# power.net
KiCad netlist of a schematic drawn in Altium Designer
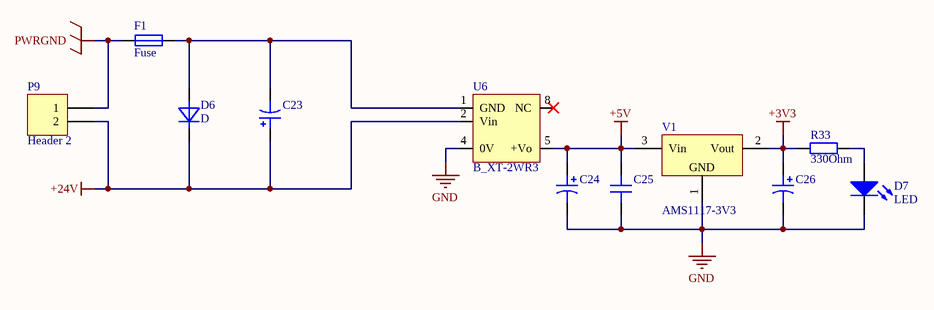
[diagram p0: power.SchDoc]

(export (version "E")
  (design (tool "Eeschema 10.0.6"))
  (components
    (comp (ref "C23")
      (value "1uF")
      (footprint "TC3528-1411")
      (description "Capacitor")
      (fields (field (name "PUBLISHER") "Altium Limited"))
      (libsource (lib "MiLib") (part "Cap Pol"))
    )
    (comp (ref "C24")
      (value "10uF")
      (footprint "TC3528-1411")
      (description "Capacitor")
      (fields (field (name "PUBLISHER") "Altium Limited"))
      (libsource (lib "MiLib") (part "Cap Pol"))
    )
    (comp (ref "C25")
      (value "100nF")
      (footprint "CAP 0805")
      (description "Non-polar capacitor")
      (fields (field (name "PUBLISHER") "Altium Limited"))
      (libsource (lib "MiLib") (part "Cap"))
    )
    (comp (ref "C26")
      (value "100uF")
      (footprint "TC7343-2917")
      (description "Capacitor")
      (fields (field (name "PUBLISHER") "Altium Limited"))
      (libsource (lib "MiLib") (part "Cap Pol"))
    )
    (comp (ref "D6") (value "D") (footprint "CD3216-1206") (libsource (lib "MiLib") (part "D")))
    (comp (ref "D7")
      (value "LED")
      (footprint "CD2012-0805")
      (fields (field (name "PUBLISHER") "Altium Limited"))
      (libsource (lib "MiLib") (part "LED"))
    )
    (comp (ref "F1")
      (value "Fuse")
      (footprint "RES 1210")
      (fields (field (name "PUBLISHER") "Altium Limited"))
      (libsource (lib "MiLib") (part "Fuse"))
    )
    (comp (ref "P9")
      (value "Header 2")
      (footprint "XT30PW-M")
      (description "Header, 2-Pin")
      (fields (field (name "PUBLISHER") "Altium Limited"))
      (libsource (lib "MiLib") (part "Header 2"))
    )
    (comp (ref "R33")
      (value "330Ohm")
      (footprint "RES 0805")
      (description "Resistor")
      (fields (field (name "PUBLISHER") "Altium Limited"))
      (libsource (lib "MiLib") (part "Res"))
    )
    (comp (ref "U6") (value "B_XT-2WR3") (footprint "B_XT-2WR3") (libsource (lib "misc") (part "B_XT-2WR3")))
    (comp (ref "V1")
      (value "AMS1117-3V3")
      (footprint "SOT-223")
      (description "三端稳压芯片")
      (fields (field (name "版权归属") "黎明电子style"))
      (libsource (lib "MiLib") (part "AMS1117"))
    )
  )
  (nets
    (net (code "1") (name "+3V3") (class "Default")
      (node (ref "C26") (pin "1") (pinfunction "1_1") (pintype "passive"))
      (node (ref "R33") (pin "1") (pinfunction "1_1") (pintype "passive"))
      (node (ref "V1") (pin "2") (pinfunction "Vout_2") (pintype "passive"))
    )
    (net (code "2") (name "+5V") (class "Default")
      (node (ref "C24") (pin "1") (pinfunction "1_1") (pintype "passive"))
      (node (ref "C25") (pin "2") (pinfunction "2_2") (pintype "passive"))
      (node (ref "U6") (pin "5") (pinfunction "+Vo_5") (pintype "passive"))
      (node (ref "V1") (pin "3") (pinfunction "Vin_3") (pintype "passive"))
    )
    (net (code "3") (name "+24V") (class "Default")
      (node (ref "C23") (pin "1") (pinfunction "1_1") (pintype "passive"))
      (node (ref "D6") (pin "2") (pinfunction "2_2") (pintype "passive"))
      (node (ref "P9") (pin "2") (pinfunction "2_2") (pintype "passive"))
      (node (ref "U6") (pin "2") (pinfunction "Vin_2") (pintype "passive"))
    )
    (net (code "4") (name "GND") (class "Default")
      (node (ref "C24") (pin "2") (pinfunction "2_2") (pintype "passive"))
      (node (ref "C25") (pin "1") (pinfunction "1_1") (pintype "passive"))
      (node (ref "C26") (pin "2") (pinfunction "2_2") (pintype "passive"))
      (node (ref "D7") (pin "2") (pinfunction "K_2") (pintype "passive"))
      (node (ref "U6") (pin "4") (pinfunction "0V_4") (pintype "passive"))
      (node (ref "V1") (pin "1") (pinfunction "GND_1") (pintype "passive"))
    )
    (net (code "5") (name "Net-(D7-A)") (class "Default")
      (node (ref "D7") (pin "1") (pinfunction "A_1") (pintype "passive"))
      (node (ref "R33") (pin "2") (pinfunction "2_2") (pintype "passive"))
    )
    (net (code "6") (name "Net-(U6-GND)") (class "Default")
      (node (ref "C23") (pin "2") (pinfunction "2_2") (pintype "passive"))
      (node (ref "D6") (pin "1") (pinfunction "1_1") (pintype "passive"))
      (node (ref "F1") (pin "2") (pinfunction "2_2") (pintype "passive"))
      (node (ref "U6") (pin "1") (pinfunction "GND_1") (pintype "passive"))
    )
    (net (code "7") (name "PWRGND") (class "Default")
      (node (ref "F1") (pin "1") (pinfunction "1_1") (pintype "passive"))
      (node (ref "P9") (pin "1") (pinfunction "1_1") (pintype "passive"))
    )
    (net (code "8") (name "unconnected-(U6-NC-Pad8)") (class "Default")
      (node (ref "U6") (pin "8") (pinfunction "NC_8") (pintype "passive+no_connect"))
    )
  )
)
